# TM1638_UNO_RDA5807FP.net
KiCad netlist of a schematic drawn in EAGLE
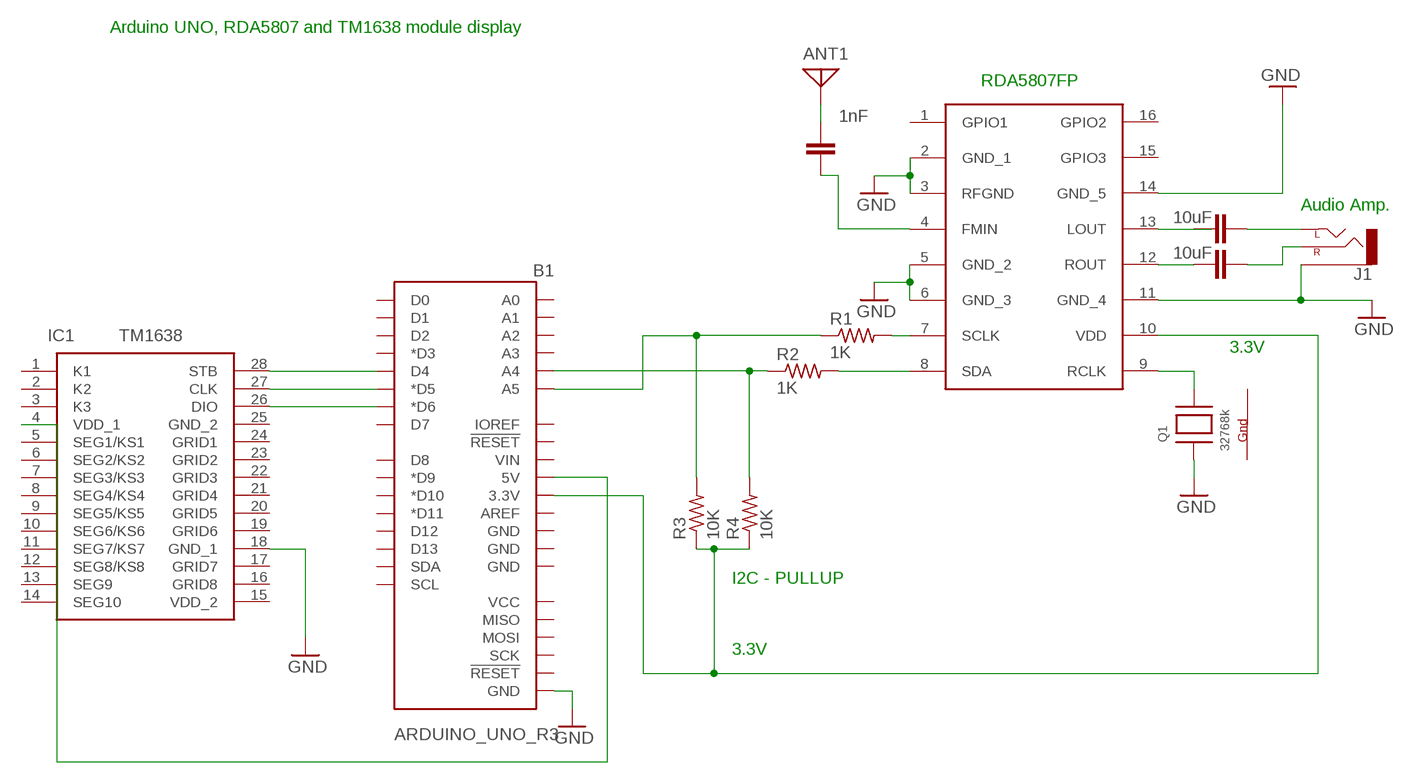
[diagram p0: schematic, sheet 1]

(export (version "E")
  (design (tool "Eeschema 10.0.6"))
  (components
    (comp (ref "ANT1")
      (value "ANTENNA")
      (footprint "eagle-import:PAD-01")
      (libsource (lib "eagle-import") (part "ANTENNA"))
    )
    (comp (ref "B1")
      (value "ARDUINO_UNO_R3")
      (footprint "eagle-import:ARDUINO_R3")
      (libsource (lib "eagle-import") (part "ARDUINO_UNO_R3"))
    )
    (comp (ref "IC1")
      (value "TM1638")
      (footprint "eagle-import:SOIC127P1020X244-28N")
      (libsource (lib "eagle-import") (part "TM1638"))
    )
    (comp (ref "J1")
      (value "AUDIO_JACK_2.5MMSPECIAL_POGO_PINS")
      (footprint "eagle-import:STEREOJACK2.5MM_SPECIAL_POGOPINS")
      (libsource (lib "eagle-import") (part "AUDIO_JACK_2.5MMSPECIAL_POGO_PINS"))
    )
    (comp (ref "Q1")
      (value "32768k")
      (footprint "eagle-import:NX3225")
      (libsource (lib "eagle-import") (part "XTAL-4-3225"))
    )
    (comp (ref "R1")
      (value "1K")
      (footprint "eagle-import:0204V")
      (libsource (lib "eagle-import") (part "R-US_0204/2V"))
    )
    (comp (ref "R2")
      (value "1K")
      (footprint "eagle-import:0204V")
      (libsource (lib "eagle-import") (part "R-US_0204/2V"))
    )
    (comp (ref "R3")
      (value "10K")
      (footprint "eagle-import:0204V")
      (libsource (lib "eagle-import") (part "R-US_0204/2V"))
    )
    (comp (ref "R4")
      (value "10K")
      (footprint "eagle-import:0204V")
      (libsource (lib "eagle-import") (part "R-US_0204/2V"))
    )
    (comp (ref "U$1")
      (value "RDA5807FPRDA5807FP")
      (footprint "eagle-import:RDA5807FP")
      (libsource (lib "eagle-import") (part "RDA5807FPRDA5807FP"))
    )
  )
  (nets
    (net (code "1") (name "/G1") (class "Default")
      (node (ref "Q1") (pin "4") (pinfunction "G1_4") (pintype "power_in"))
    )
    (net (code "2") (name "/G2") (class "Default")
      (node (ref "Q1") (pin "2") (pinfunction "G2_2") (pintype "power_in"))
    )
    (net (code "3") (name "GND") (class "Default")
      (node (ref "B1") (pin "GND@1") (pinfunction "GND_GND@1") (pintype "bidirectional"))
      (node (ref "IC1") (pin "18") (pinfunction "GND_1_18") (pintype "bidirectional"))
      (node (ref "J1") (pin "RING1") (pinfunction "SLEEVE_RING1") (pintype "bidirectional"))
      (node (ref "Q1") (pin "1") (pinfunction "X1_1") (pintype "bidirectional"))
      (node (ref "U$1") (pin "11") (pinfunction "GND_4_11") (pintype "bidirectional"))
      (node (ref "U$1") (pin "14") (pinfunction "GND_5_14") (pintype "bidirectional"))
      (node (ref "U$1") (pin "2") (pinfunction "GND_1_2") (pintype "bidirectional"))
      (node (ref "U$1") (pin "3") (pinfunction "RFGND_3") (pintype "bidirectional"))
      (node (ref "U$1") (pin "5") (pinfunction "GND_2_5") (pintype "bidirectional"))
      (node (ref "U$1") (pin "6") (pinfunction "GND_3_6") (pintype "bidirectional"))
    )
    (net (code "4") (name "Net-(B1-*D5)") (class "Default")
      (node (ref "B1") (pin "D5") (pinfunction "*D5_D5") (pintype "bidirectional"))
      (node (ref "IC1") (pin "27") (pinfunction "CLK_27") (pintype "bidirectional"))
    )
    (net (code "5") (name "Net-(B1-*D6)") (class "Default")
      (node (ref "B1") (pin "D6") (pinfunction "*D6_D6") (pintype "bidirectional"))
      (node (ref "IC1") (pin "26") (pinfunction "DIO_26") (pintype "bidirectional"))
    )
    (net (code "6") (name "Net-(B1-PadA4)") (class "Default")
      (node (ref "B1") (pin "A4") (pinfunction "A4_A4") (pintype "bidirectional"))
      (node (ref "R2") (pin "1") (pinfunction "1_1") (pintype "passive"))
      (node (ref "R4") (pin "2") (pinfunction "2_2") (pintype "passive"))
    )
    (net (code "7") (name "Net-(B1-PadA5)") (class "Default")
      (node (ref "B1") (pin "A5") (pinfunction "A5_A5") (pintype "bidirectional"))
      (node (ref "R1") (pin "1") (pinfunction "1_1") (pintype "passive"))
      (node (ref "R3") (pin "2") (pinfunction "2_2") (pintype "passive"))
    )
    (net (code "8") (name "Net-(IC1-STB)") (class "Default")
      (node (ref "B1") (pin "D4") (pinfunction "D4_D4") (pintype "bidirectional"))
      (node (ref "IC1") (pin "28") (pinfunction "STB_28") (pintype "bidirectional"))
    )
    (net (code "9") (name "Net-(IC1-VDD_1)") (class "Default")
      (node (ref "B1") (pin "5V") (pinfunction "5V_5V") (pintype "bidirectional"))
      (node (ref "IC1") (pin "4") (pinfunction "VDD_1_4") (pintype "bidirectional"))
    )
    (net (code "10") (name "Net-(Q1-X2)") (class "Default")
      (node (ref "Q1") (pin "3") (pinfunction "X2_3") (pintype "bidirectional"))
      (node (ref "U$1") (pin "9") (pinfunction "RCLK_9") (pintype "bidirectional"))
    )
    (net (code "11") (name "Net-(U$1-SCLK)") (class "Default")
      (node (ref "R1") (pin "2") (pinfunction "2_2") (pintype "passive"))
      (node (ref "U$1") (pin "7") (pinfunction "SCLK_7") (pintype "bidirectional"))
    )
    (net (code "12") (name "Net-(U$1-SDA)") (class "Default")
      (node (ref "R2") (pin "2") (pinfunction "2_2") (pintype "passive"))
      (node (ref "U$1") (pin "8") (pinfunction "SDA_8") (pintype "bidirectional"))
    )
    (net (code "13") (name "Net-(U$1-VDD)") (class "Default")
      (node (ref "B1") (pin "3.3V") (pinfunction "3.3V_3.3V") (pintype "bidirectional"))
      (node (ref "R3") (pin "1") (pinfunction "1_1") (pintype "passive"))
      (node (ref "R4") (pin "1") (pinfunction "1_1") (pintype "passive"))
      (node (ref "U$1") (pin "10") (pinfunction "VDD_10") (pintype "bidirectional"))
    )
    (net (code "14") (name "unconnected-(ANT1-Pad1)") (class "Default")
      (node (ref "ANT1") (pin "1") (pinfunction "1_1") (pintype "output"))
    )
    (net (code "15") (name "unconnected-(B1-*D3-PadD3)") (class "Default")
      (node (ref "B1") (pin "D3") (pinfunction "*D3_D3") (pintype "bidirectional"))
    )
    (net (code "16") (name "unconnected-(B1-*D9-PadD9)") (class "Default")
      (node (ref "B1") (pin "D9") (pinfunction "*D9_D9") (pintype "bidirectional"))
    )
    (net (code "17") (name "unconnected-(B1-*D10-PadD10)") (class "Default")
      (node (ref "B1") (pin "D10") (pinfunction "*D10_D10") (pintype "bidirectional"))
    )
    (net (code "18") (name "unconnected-(B1-*D11-PadD11)") (class "Default")
      (node (ref "B1") (pin "D11") (pinfunction "*D11_D11") (pintype "bidirectional"))
    )
    (net (code "19") (name "unconnected-(B1-GND-PadGND@2)") (class "Default")
      (node (ref "B1") (pin "GND@2") (pinfunction "GND_GND@2") (pintype "bidirectional"))
    )
    (net (code "20") (name "unconnected-(B1-GND-PadGND@3)") (class "Default")
      (node (ref "B1") (pin "GND@3") (pinfunction "GND_GND@3") (pintype "bidirectional"))
    )
    (net (code "21") (name "unconnected-(B1-GND-PadGND@4)") (class "Default")
      (node (ref "B1") (pin "GND@4") (pinfunction "GND_GND@4") (pintype "bidirectional"))
    )
    (net (code "22") (name "unconnected-(B1-PadA0)") (class "Default")
      (node (ref "B1") (pin "A0") (pinfunction "A0_A0") (pintype "bidirectional"))
    )
    (net (code "23") (name "unconnected-(B1-PadA1)") (class "Default")
      (node (ref "B1") (pin "A1") (pinfunction "A1_A1") (pintype "bidirectional"))
    )
    (net (code "24") (name "unconnected-(B1-PadA2)") (class "Default")
      (node (ref "B1") (pin "A2") (pinfunction "A2_A2") (pintype "bidirectional"))
    )
    (net (code "25") (name "unconnected-(B1-PadA3)") (class "Default")
      (node (ref "B1") (pin "A3") (pinfunction "A3_A3") (pintype "bidirectional"))
    )
    (net (code "26") (name "unconnected-(B1-PadAREF)") (class "Default")
      (node (ref "B1") (pin "AREF") (pinfunction "AREF_AREF") (pintype "bidirectional"))
    )
    (net (code "27") (name "unconnected-(B1-PadD0)") (class "Default")
      (node (ref "B1") (pin "D0") (pinfunction "D0_D0") (pintype "bidirectional"))
    )
    (net (code "28") (name "unconnected-(B1-PadD1)") (class "Default")
      (node (ref "B1") (pin "D1") (pinfunction "D1_D1") (pintype "bidirectional"))
    )
    (net (code "29") (name "unconnected-(B1-PadD2)") (class "Default")
      (node (ref "B1") (pin "D2") (pinfunction "D2_D2") (pintype "bidirectional"))
    )
    (net (code "30") (name "unconnected-(B1-PadD7)") (class "Default")
      (node (ref "B1") (pin "D7") (pinfunction "D7_D7") (pintype "bidirectional"))
    )
    (net (code "31") (name "unconnected-(B1-PadD8)") (class "Default")
      (node (ref "B1") (pin "D8") (pinfunction "D8_D8") (pintype "bidirectional"))
    )
    (net (code "32") (name "unconnected-(B1-PadD12)") (class "Default")
      (node (ref "B1") (pin "D12") (pinfunction "D12_D12") (pintype "bidirectional"))
    )
    (net (code "33") (name "unconnected-(B1-PadD13)") (class "Default")
      (node (ref "B1") (pin "D13") (pinfunction "D13_D13") (pintype "bidirectional"))
    )
    (net (code "34") (name "unconnected-(B1-PadIOREF)") (class "Default")
      (node (ref "B1") (pin "IOREF") (pinfunction "IOREF_IOREF") (pintype "bidirectional"))
    )
    (net (code "35") (name "unconnected-(B1-PadMISO)") (class "Default")
      (node (ref "B1") (pin "MISO") (pinfunction "MISO_MISO") (pintype "bidirectional"))
    )
    (net (code "36") (name "unconnected-(B1-PadMOSI)") (class "Default")
      (node (ref "B1") (pin "MOSI") (pinfunction "MOSI_MOSI") (pintype "bidirectional"))
    )
    (net (code "37") (name "unconnected-(B1-PadSCK)") (class "Default")
      (node (ref "B1") (pin "SCK") (pinfunction "SCK_SCK") (pintype "bidirectional"))
    )
    (net (code "38") (name "unconnected-(B1-PadSCL)") (class "Default")
      (node (ref "B1") (pin "SCL") (pinfunction "SCL_SCL") (pintype "bidirectional"))
    )
    (net (code "39") (name "unconnected-(B1-PadSDA)") (class "Default")
      (node (ref "B1") (pin "SDA") (pinfunction "SDA_SDA") (pintype "bidirectional"))
    )
    (net (code "40") (name "unconnected-(B1-PadVCC)") (class "Default")
      (node (ref "B1") (pin "VCC") (pinfunction "VCC_VCC") (pintype "bidirectional"))
    )
    (net (code "41") (name "unconnected-(B1-PadVIN)") (class "Default")
      (node (ref "B1") (pin "VIN") (pinfunction "VIN_VIN") (pintype "bidirectional"))
    )
    (net (code "42") (name "unconnected-(B1-~{RESET}-PadRESET@1)") (class "Default")
      (node (ref "B1") (pin "RESET@1") (pinfunction "~{RESET}_RESET@1") (pintype "bidirectional"))
    )
    (net (code "43") (name "unconnected-(B1-~{RESET}-PadRESET@2)") (class "Default")
      (node (ref "B1") (pin "RESET@2") (pinfunction "~{RESET}_RESET@2") (pintype "bidirectional"))
    )
    (net (code "44") (name "unconnected-(IC1-GND_2-Pad25)") (class "Default")
      (node (ref "IC1") (pin "25") (pinfunction "GND_2_25") (pintype "bidirectional"))
    )
    (net (code "45") (name "unconnected-(IC1-GRID1-Pad24)") (class "Default")
      (node (ref "IC1") (pin "24") (pinfunction "GRID1_24") (pintype "bidirectional"))
    )
    (net (code "46") (name "unconnected-(IC1-GRID2-Pad23)") (class "Default")
      (node (ref "IC1") (pin "23") (pinfunction "GRID2_23") (pintype "bidirectional"))
    )
    (net (code "47") (name "unconnected-(IC1-GRID3-Pad22)") (class "Default")
      (node (ref "IC1") (pin "22") (pinfunction "GRID3_22") (pintype "bidirectional"))
    )
    (net (code "48") (name "unconnected-(IC1-GRID4-Pad21)") (class "Default")
      (node (ref "IC1") (pin "21") (pinfunction "GRID4_21") (pintype "bidirectional"))
    )
    (net (code "49") (name "unconnected-(IC1-GRID5-Pad20)") (class "Default")
      (node (ref "IC1") (pin "20") (pinfunction "GRID5_20") (pintype "bidirectional"))
    )
    (net (code "50") (name "unconnected-(IC1-GRID6-Pad19)") (class "Default")
      (node (ref "IC1") (pin "19") (pinfunction "GRID6_19") (pintype "bidirectional"))
    )
    (net (code "51") (name "unconnected-(IC1-GRID7-Pad17)") (class "Default")
      (node (ref "IC1") (pin "17") (pinfunction "GRID7_17") (pintype "bidirectional"))
    )
    (net (code "52") (name "unconnected-(IC1-GRID8-Pad16)") (class "Default")
      (node (ref "IC1") (pin "16") (pinfunction "GRID8_16") (pintype "bidirectional"))
    )
    (net (code "53") (name "unconnected-(IC1-K1-Pad1)") (class "Default")
      (node (ref "IC1") (pin "1") (pinfunction "K1_1") (pintype "bidirectional"))
    )
    (net (code "54") (name "unconnected-(IC1-K2-Pad2)") (class "Default")
      (node (ref "IC1") (pin "2") (pinfunction "K2_2") (pintype "bidirectional"))
    )
    (net (code "55") (name "unconnected-(IC1-K3-Pad3)") (class "Default")
      (node (ref "IC1") (pin "3") (pinfunction "K3_3") (pintype "bidirectional"))
    )
    (net (code "56") (name "unconnected-(IC1-SEG1{slash}KS1-Pad5)") (class "Default")
      (node (ref "IC1") (pin "5") (pinfunction "SEG1/KS1_5") (pintype "bidirectional"))
    )
    (net (code "57") (name "unconnected-(IC1-SEG2{slash}KS2-Pad6)") (class "Default")
      (node (ref "IC1") (pin "6") (pinfunction "SEG2/KS2_6") (pintype "bidirectional"))
    )
    (net (code "58") (name "unconnected-(IC1-SEG3{slash}KS3-Pad7)") (class "Default")
      (node (ref "IC1") (pin "7") (pinfunction "SEG3/KS3_7") (pintype "bidirectional"))
    )
    (net (code "59") (name "unconnected-(IC1-SEG4{slash}KS4-Pad8)") (class "Default")
      (node (ref "IC1") (pin "8") (pinfunction "SEG4/KS4_8") (pintype "bidirectional"))
    )
    (net (code "60") (name "unconnected-(IC1-SEG5{slash}KS5-Pad9)") (class "Default")
      (node (ref "IC1") (pin "9") (pinfunction "SEG5/KS5_9") (pintype "bidirectional"))
    )
    (net (code "61") (name "unconnected-(IC1-SEG6{slash}KS6-Pad10)") (class "Default")
      (node (ref "IC1") (pin "10") (pinfunction "SEG6/KS6_10") (pintype "bidirectional"))
    )
    (net (code "62") (name "unconnected-(IC1-SEG7{slash}KS7-Pad11)") (class "Default")
      (node (ref "IC1") (pin "11") (pinfunction "SEG7/KS7_11") (pintype "bidirectional"))
    )
    (net (code "63") (name "unconnected-(IC1-SEG8{slash}KS8-Pad12)") (class "Default")
      (node (ref "IC1") (pin "12") (pinfunction "SEG8/KS8_12") (pintype "bidirectional"))
    )
    (net (code "64") (name "unconnected-(IC1-SEG9-Pad13)") (class "Default")
      (node (ref "IC1") (pin "13") (pinfunction "SEG9_13") (pintype "bidirectional"))
    )
    (net (code "65") (name "unconnected-(IC1-SEG10-Pad14)") (class "Default")
      (node (ref "IC1") (pin "14") (pinfunction "SEG10_14") (pintype "bidirectional"))
    )
    (net (code "66") (name "unconnected-(IC1-VDD_2-Pad15)") (class "Default")
      (node (ref "IC1") (pin "15") (pinfunction "VDD_2_15") (pintype "bidirectional"))
    )
    (net (code "67") (name "unconnected-(J1-LEFT-PadSHIELD)") (class "Default")
      (node (ref "J1") (pin "SHIELD") (pinfunction "LEFT_SHIELD") (pintype "bidirectional"))
    )
    (net (code "68") (name "unconnected-(J1-RIGHT-PadTIP)") (class "Default")
      (node (ref "J1") (pin "TIP") (pinfunction "RIGHT_TIP") (pintype "bidirectional"))
    )
    (net (code "69") (name "unconnected-(U$1-FMIN-Pad4)") (class "Default")
      (node (ref "U$1") (pin "4") (pinfunction "FMIN_4") (pintype "bidirectional"))
    )
    (net (code "70") (name "unconnected-(U$1-GPIO1-Pad1)") (class "Default")
      (node (ref "U$1") (pin "1") (pinfunction "GPIO1_1") (pintype "bidirectional"))
    )
    (net (code "71") (name "unconnected-(U$1-GPIO2-Pad16)") (class "Default")
      (node (ref "U$1") (pin "16") (pinfunction "GPIO2_16") (pintype "bidirectional"))
    )
    (net (code "72") (name "unconnected-(U$1-GPIO3-Pad15)") (class "Default")
      (node (ref "U$1") (pin "15") (pinfunction "GPIO3_15") (pintype "bidirectional"))
    )
    (net (code "73") (name "unconnected-(U$1-LOUT-Pad13)") (class "Default")
      (node (ref "U$1") (pin "13") (pinfunction "LOUT_13") (pintype "bidirectional"))
    )
    (net (code "74") (name "unconnected-(U$1-ROUT-Pad12)") (class "Default")
      (node (ref "U$1") (pin "12") (pinfunction "ROUT_12") (pintype "bidirectional"))
    )
  )
)
